# dual_motor_driver_v6.net
KiCad netlist of a schematic drawn in EAGLE
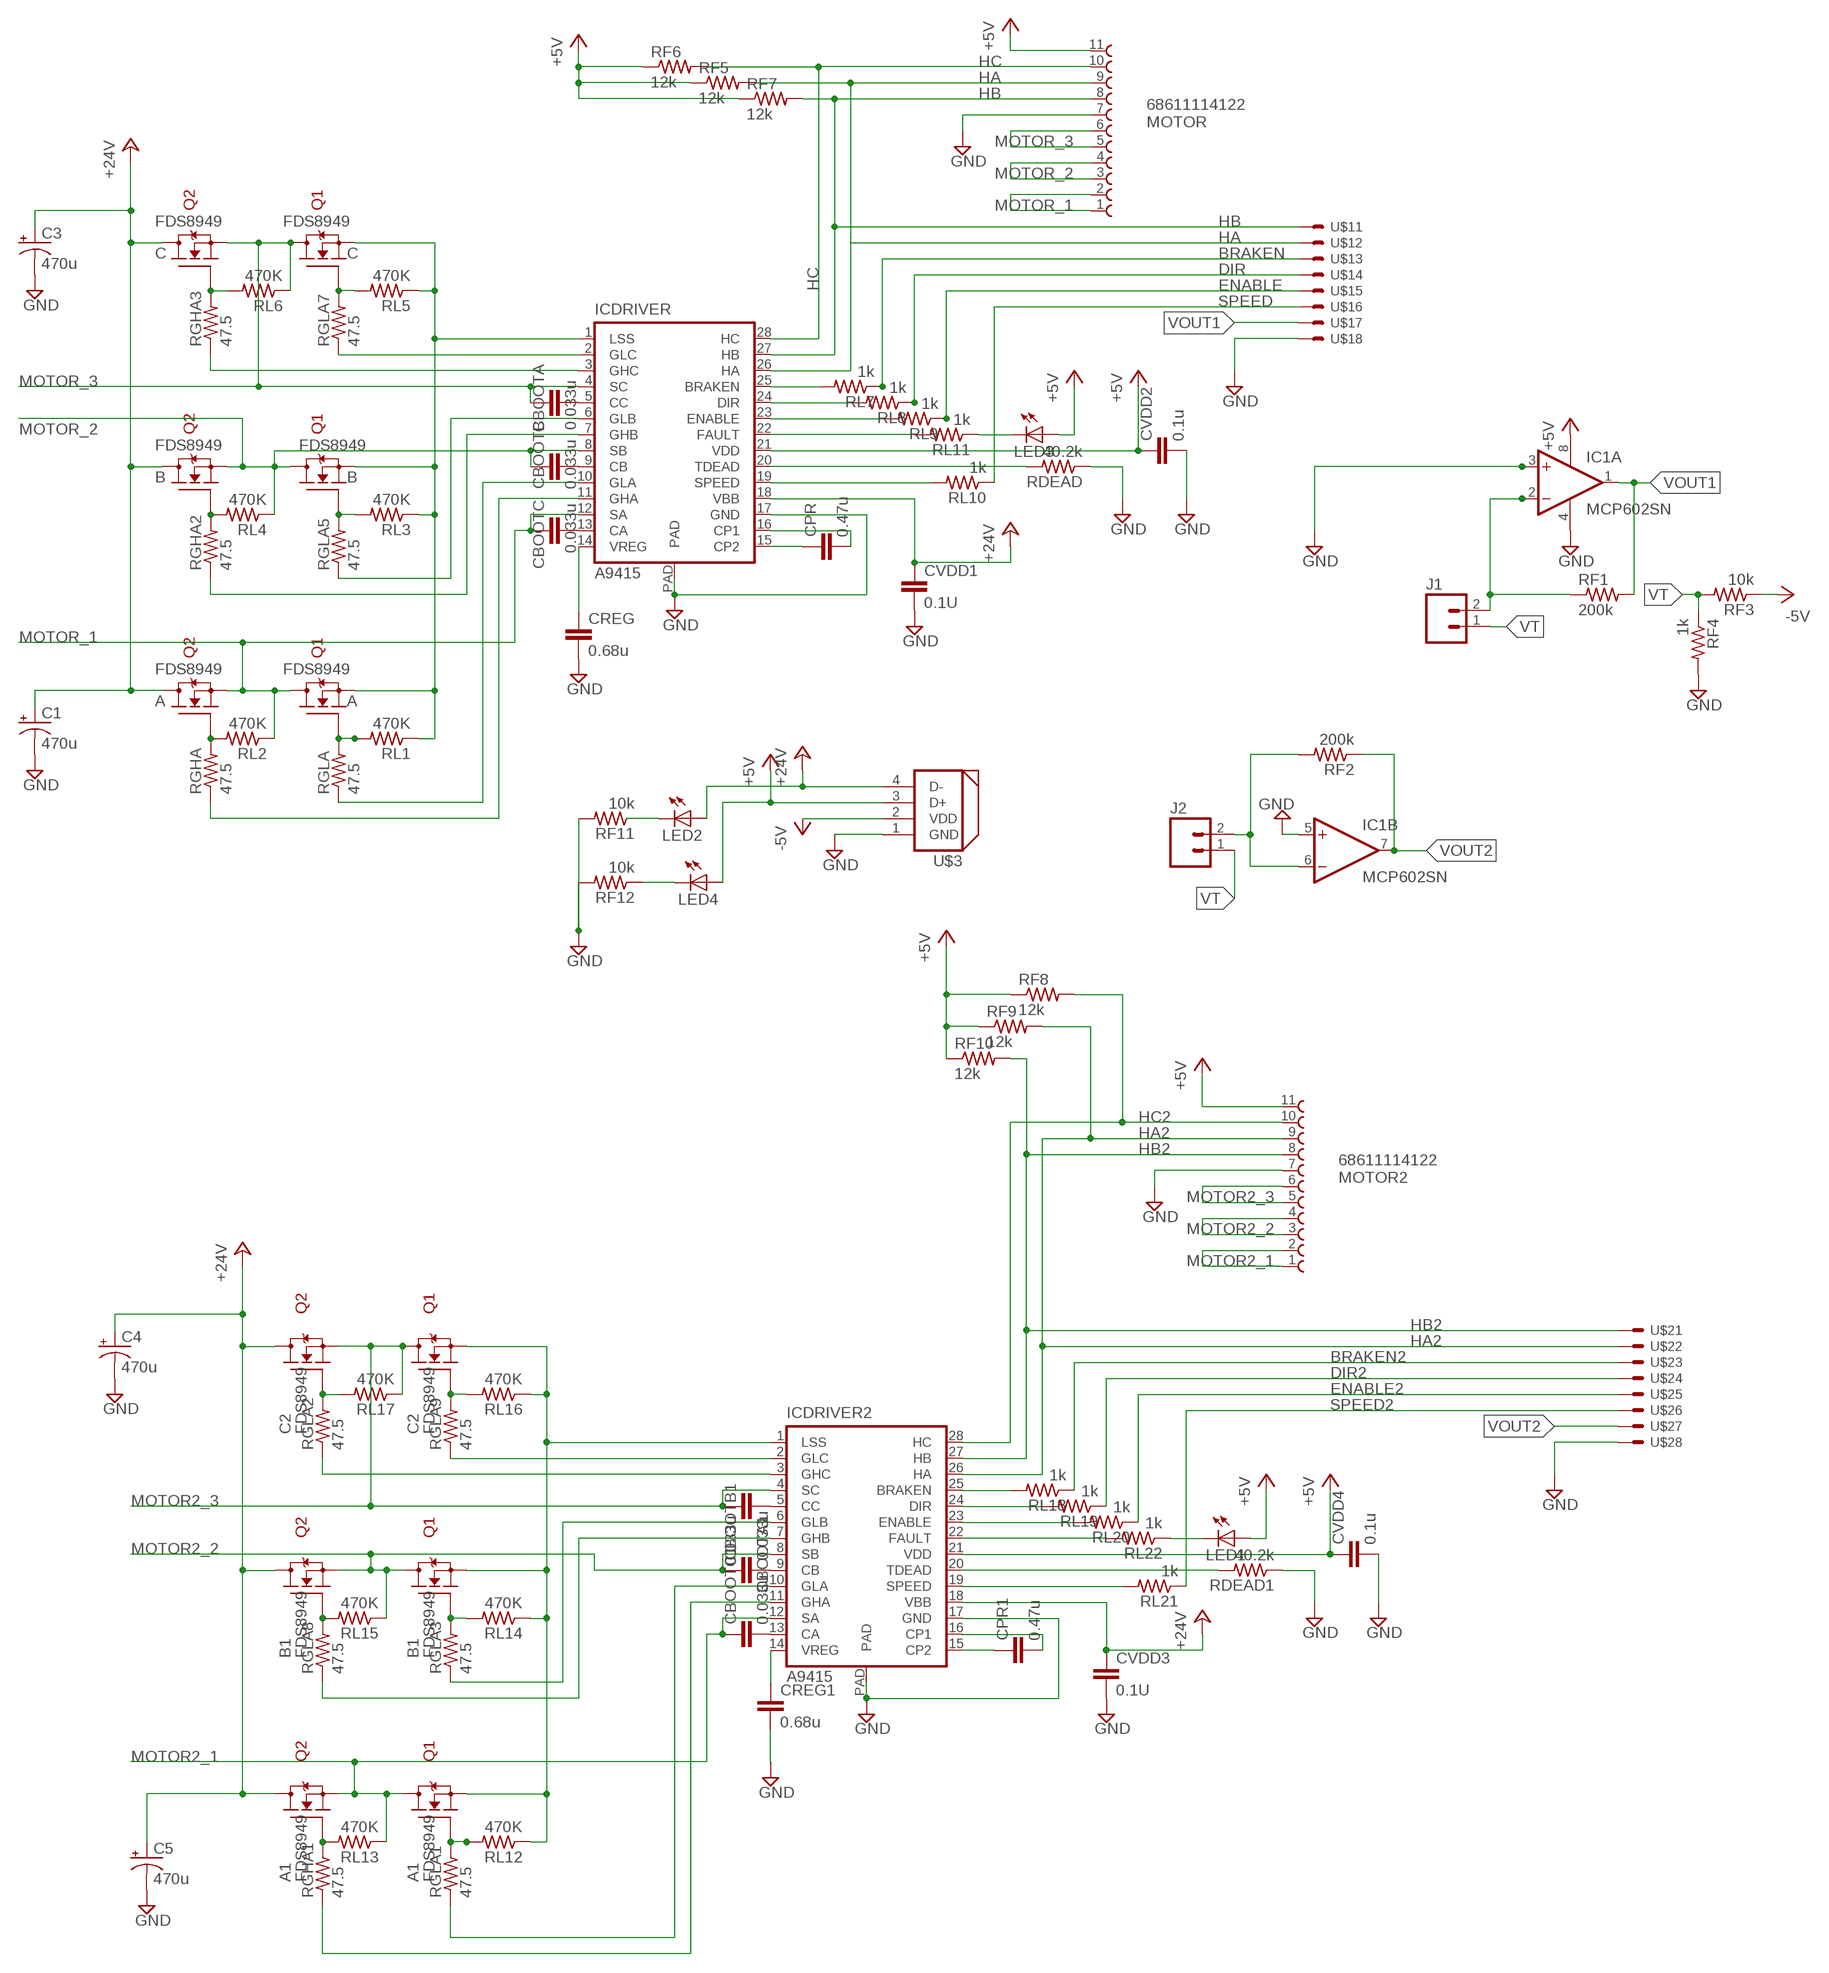
[diagram p0: schematic, sheet 1]

(export (version "E")
  (design (tool "Eeschema 10.0.6"))
  (components
    (comp (ref "A")
      (value "FDS8949")
      (footprint "eagle-import:SOIC8")
      (libsource (lib "eagle-import") (part "FDS8949"))
    )
    (comp (ref "A1")
      (value "FDS8949")
      (footprint "eagle-import:SOIC8")
      (libsource (lib "eagle-import") (part "FDS8949"))
    )
    (comp (ref "B")
      (value "FDS8949")
      (footprint "eagle-import:SOIC8")
      (libsource (lib "eagle-import") (part "FDS8949"))
    )
    (comp (ref "B1")
      (value "FDS8949")
      (footprint "eagle-import:SOIC8")
      (libsource (lib "eagle-import") (part "FDS8949"))
    )
    (comp (ref "C")
      (value "FDS8949")
      (footprint "eagle-import:SOIC8")
      (libsource (lib "eagle-import") (part "FDS8949"))
    )
    (comp (ref "C1")
      (value "470u")
      (footprint "eagle-import:140CLH-1010")
      (libsource (lib "eagle-import") (part "CPOL-US140CLH-1010"))
    )
    (comp (ref "C2")
      (value "FDS8949")
      (footprint "eagle-import:SOIC8")
      (libsource (lib "eagle-import") (part "FDS8949"))
    )
    (comp (ref "C3")
      (value "470u")
      (footprint "eagle-import:140CLH-1010")
      (libsource (lib "eagle-import") (part "CPOL-US140CLH-1010"))
    )
    (comp (ref "C4")
      (value "470u")
      (footprint "eagle-import:140CLH-1010")
      (libsource (lib "eagle-import") (part "CPOL-US140CLH-1010"))
    )
    (comp (ref "C5")
      (value "470u")
      (footprint "eagle-import:140CLH-1010")
      (libsource (lib "eagle-import") (part "CPOL-US140CLH-1010"))
    )
    (comp (ref "CBOOTA")
      (value "0.033u")
      (footprint "eagle-import:C0805")
      (libsource (lib "eagle-import") (part "C-EUC0805"))
    )
    (comp (ref "CBOOTA1")
      (value "0.033u")
      (footprint "eagle-import:C0805")
      (libsource (lib "eagle-import") (part "C-EUC0805"))
    )
    (comp (ref "CBOOTB")
      (value "0.033u")
      (footprint "eagle-import:C0805")
      (libsource (lib "eagle-import") (part "C-EUC0805"))
    )
    (comp (ref "CBOOTB1")
      (value "0.033u")
      (footprint "eagle-import:C0805")
      (libsource (lib "eagle-import") (part "C-EUC0805"))
    )
    (comp (ref "CBOOTC")
      (value "0.033u")
      (footprint "eagle-import:C0805")
      (libsource (lib "eagle-import") (part "C-EUC0805"))
    )
    (comp (ref "CBOOTC1")
      (value "0.033u")
      (footprint "eagle-import:C0805")
      (libsource (lib "eagle-import") (part "C-EUC0805"))
    )
    (comp (ref "CPR")
      (value "0.47u")
      (footprint "eagle-import:C0805")
      (libsource (lib "eagle-import") (part "C-EUC0805"))
    )
    (comp (ref "CPR1")
      (value "0.47u")
      (footprint "eagle-import:C0805")
      (libsource (lib "eagle-import") (part "C-EUC0805"))
    )
    (comp (ref "CREG")
      (value "0.68u")
      (footprint "eagle-import:C0805")
      (libsource (lib "eagle-import") (part "C-EUC0805"))
    )
    (comp (ref "CREG1")
      (value "0.68u")
      (footprint "eagle-import:C0805")
      (libsource (lib "eagle-import") (part "C-EUC0805"))
    )
    (comp (ref "CVDD1")
      (value "0.1U")
      (footprint "eagle-import:C0805")
      (libsource (lib "eagle-import") (part "C-EUC0805"))
    )
    (comp (ref "CVDD2")
      (value "0.1u")
      (footprint "eagle-import:C0805")
      (libsource (lib "eagle-import") (part "C-EUC0805"))
    )
    (comp (ref "CVDD3")
      (value "0.1U")
      (footprint "eagle-import:C0805")
      (libsource (lib "eagle-import") (part "C-EUC0805"))
    )
    (comp (ref "CVDD4")
      (value "0.1u")
      (footprint "eagle-import:C0805")
      (libsource (lib "eagle-import") (part "C-EUC0805"))
    )
    (comp (ref "IC1")
      (value "MCP602SN")
      (footprint "eagle-import:SO08")
      (libsource (lib "eagle-import") (part "MCP602SN"))
    )
    (comp (ref "ICDRIVER")
      (value "A9415")
      (footprint "eagle-import:TSSOP28")
      (libsource (lib "eagle-import") (part "A9415"))
    )
    (comp (ref "ICDRIVER2")
      (value "A9415")
      (footprint "eagle-import:TSSOP28")
      (libsource (lib "eagle-import") (part "A9415"))
    )
    (comp (ref "J1")
      (value "M02PTH")
      (footprint "eagle-import:1X02")
      (libsource (lib "eagle-import") (part "M02PTH"))
    )
    (comp (ref "J2")
      (value "M02PTH")
      (footprint "eagle-import:1X02")
      (libsource (lib "eagle-import") (part "M02PTH"))
    )
    (comp (ref "LED1")
      (value "LEDCHIPLED_0805")
      (footprint "eagle-import:CHIPLED_0805")
      (libsource (lib "eagle-import") (part "LEDCHIPLED_0805"))
    )
    (comp (ref "LED2")
      (value "LEDCHIPLED_0805")
      (footprint "eagle-import:CHIPLED_0805")
      (libsource (lib "eagle-import") (part "LEDCHIPLED_0805"))
    )
    (comp (ref "LED3")
      (value "LEDCHIPLED_0805")
      (footprint "eagle-import:CHIPLED_0805")
      (libsource (lib "eagle-import") (part "LEDCHIPLED_0805"))
    )
    (comp (ref "LED4")
      (value "LEDCHIPLED_0805")
      (footprint "eagle-import:CHIPLED_0805")
      (libsource (lib "eagle-import") (part "LEDCHIPLED_0805"))
    )
    (comp (ref "MOTOR")
      (value "68611114122")
      (footprint "eagle-import:68611114122")
      (libsource (lib "eagle-import") (part "68611114122"))
    )
    (comp (ref "MOTOR2")
      (value "68611114122")
      (footprint "eagle-import:68611114122")
      (libsource (lib "eagle-import") (part "68611114122"))
    )
    (comp (ref "RDEAD")
      (value "40.2k")
      (footprint "eagle-import:R0805")
      (libsource (lib "eagle-import") (part "R-US_R0805"))
    )
    (comp (ref "RDEAD1")
      (value "40.2k")
      (footprint "eagle-import:R0805")
      (libsource (lib "eagle-import") (part "R-US_R0805"))
    )
    (comp (ref "RF1")
      (value "200k")
      (footprint "eagle-import:R0805")
      (libsource (lib "eagle-import") (part "R-US_R0805"))
    )
    (comp (ref "RF2")
      (value "200k")
      (footprint "eagle-import:R0805")
      (libsource (lib "eagle-import") (part "R-US_R0805"))
    )
    (comp (ref "RF3")
      (value "10k")
      (footprint "eagle-import:R0805")
      (libsource (lib "eagle-import") (part "R-US_R0805"))
    )
    (comp (ref "RF4")
      (value "1k")
      (footprint "eagle-import:R0805")
      (libsource (lib "eagle-import") (part "R-US_R0805"))
    )
    (comp (ref "RF5")
      (value "12k")
      (footprint "eagle-import:R0805")
      (libsource (lib "eagle-import") (part "R-US_R0805"))
    )
    (comp (ref "RF6")
      (value "12k")
      (footprint "eagle-import:R0805")
      (libsource (lib "eagle-import") (part "R-US_R0805"))
    )
    (comp (ref "RF7")
      (value "12k")
      (footprint "eagle-import:R0805")
      (libsource (lib "eagle-import") (part "R-US_R0805"))
    )
    (comp (ref "RF8")
      (value "12k")
      (footprint "eagle-import:R0805")
      (libsource (lib "eagle-import") (part "R-US_R0805"))
    )
    (comp (ref "RF9")
      (value "12k")
      (footprint "eagle-import:R0805")
      (libsource (lib "eagle-import") (part "R-US_R0805"))
    )
    (comp (ref "RF10")
      (value "12k")
      (footprint "eagle-import:R0805")
      (libsource (lib "eagle-import") (part "R-US_R0805"))
    )
    (comp (ref "RF11")
      (value "10k")
      (footprint "eagle-import:R0805")
      (libsource (lib "eagle-import") (part "R-US_R0805"))
    )
    (comp (ref "RF12")
      (value "10k")
      (footprint "eagle-import:R0805")
      (libsource (lib "eagle-import") (part "R-US_R0805"))
    )
    (comp (ref "RGHA")
      (value "47.5")
      (footprint "eagle-import:R0805")
      (libsource (lib "eagle-import") (part "R-US_R0805"))
    )
    (comp (ref "RGHA1")
      (value "47.5")
      (footprint "eagle-import:R0805")
      (libsource (lib "eagle-import") (part "R-US_R0805"))
    )
    (comp (ref "RGHA2")
      (value "47.5")
      (footprint "eagle-import:R0805")
      (libsource (lib "eagle-import") (part "R-US_R0805"))
    )
    (comp (ref "RGHA3")
      (value "47.5")
      (footprint "eagle-import:R0805")
      (libsource (lib "eagle-import") (part "R-US_R0805"))
    )
    (comp (ref "RGLA")
      (value "47.5")
      (footprint "eagle-import:R0805")
      (libsource (lib "eagle-import") (part "R-US_R0805"))
    )
    (comp (ref "RGLA1")
      (value "47.5")
      (footprint "eagle-import:R0805")
      (libsource (lib "eagle-import") (part "R-US_R0805"))
    )
    (comp (ref "RGLA2")
      (value "47.5")
      (footprint "eagle-import:R0805")
      (libsource (lib "eagle-import") (part "R-US_R0805"))
    )
    (comp (ref "RGLA3")
      (value "47.5")
      (footprint "eagle-import:R0805")
      (libsource (lib "eagle-import") (part "R-US_R0805"))
    )
    (comp (ref "RGLA5")
      (value "47.5")
      (footprint "eagle-import:R0805")
      (libsource (lib "eagle-import") (part "R-US_R0805"))
    )
    (comp (ref "RGLA7")
      (value "47.5")
      (footprint "eagle-import:R0805")
      (libsource (lib "eagle-import") (part "R-US_R0805"))
    )
    (comp (ref "RGLA8")
      (value "47.5")
      (footprint "eagle-import:R0805")
      (libsource (lib "eagle-import") (part "R-US_R0805"))
    )
    (comp (ref "RGLA9")
      (value "47.5")
      (footprint "eagle-import:R0805")
      (libsource (lib "eagle-import") (part "R-US_R0805"))
    )
    (comp (ref "RL1")
      (value "470K")
      (footprint "eagle-import:R0805")
      (libsource (lib "eagle-import") (part "R-US_R0805"))
    )
    (comp (ref "RL2")
      (value "470K")
      (footprint "eagle-import:R0805")
      (libsource (lib "eagle-import") (part "R-US_R0805"))
    )
    (comp (ref "RL3")
      (value "470K")
      (footprint "eagle-import:R0805")
      (libsource (lib "eagle-import") (part "R-US_R0805"))
    )
    (comp (ref "RL4")
      (value "470K")
      (footprint "eagle-import:R0805")
      (libsource (lib "eagle-import") (part "R-US_R0805"))
    )
    (comp (ref "RL5")
      (value "470K")
      (footprint "eagle-import:R0805")
      (libsource (lib "eagle-import") (part "R-US_R0805"))
    )
    (comp (ref "RL6")
      (value "470K")
      (footprint "eagle-import:R0805")
      (libsource (lib "eagle-import") (part "R-US_R0805"))
    )
    (comp (ref "RL7")
      (value "1k")
      (footprint "eagle-import:R0805")
      (libsource (lib "eagle-import") (part "R-US_R0805"))
    )
    (comp (ref "RL8")
      (value "1k")
      (footprint "eagle-import:R0805")
      (libsource (lib "eagle-import") (part "R-US_R0805"))
    )
    (comp (ref "RL9")
      (value "1k")
      (footprint "eagle-import:R0805")
      (libsource (lib "eagle-import") (part "R-US_R0805"))
    )
    (comp (ref "RL10")
      (value "1k")
      (footprint "eagle-import:R0805")
      (libsource (lib "eagle-import") (part "R-US_R0805"))
    )
    (comp (ref "RL11")
      (value "1k")
      (footprint "eagle-import:R0805")
      (libsource (lib "eagle-import") (part "R-US_R0805"))
    )
    (comp (ref "RL12")
      (value "470K")
      (footprint "eagle-import:R0805")
      (libsource (lib "eagle-import") (part "R-US_R0805"))
    )
    (comp (ref "RL13")
      (value "470K")
      (footprint "eagle-import:R0805")
      (libsource (lib "eagle-import") (part "R-US_R0805"))
    )
    (comp (ref "RL14")
      (value "470K")
      (footprint "eagle-import:R0805")
      (libsource (lib "eagle-import") (part "R-US_R0805"))
    )
    (comp (ref "RL15")
      (value "470K")
      (footprint "eagle-import:R0805")
      (libsource (lib "eagle-import") (part "R-US_R0805"))
    )
    (comp (ref "RL16")
      (value "470K")
      (footprint "eagle-import:R0805")
      (libsource (lib "eagle-import") (part "R-US_R0805"))
    )
    (comp (ref "RL17")
      (value "470K")
      (footprint "eagle-import:R0805")
      (libsource (lib "eagle-import") (part "R-US_R0805"))
    )
    (comp (ref "RL18")
      (value "1k")
      (footprint "eagle-import:R0805")
      (libsource (lib "eagle-import") (part "R-US_R0805"))
    )
    (comp (ref "RL19")
      (value "1k")
      (footprint "eagle-import:R0805")
      (libsource (lib "eagle-import") (part "R-US_R0805"))
    )
    (comp (ref "RL20")
      (value "1k")
      (footprint "eagle-import:R0805")
      (libsource (lib "eagle-import") (part "R-US_R0805"))
    )
    (comp (ref "RL21")
      (value "1k")
      (footprint "eagle-import:R0805")
      (libsource (lib "eagle-import") (part "R-US_R0805"))
    )
    (comp (ref "RL22")
      (value "1k")
      (footprint "eagle-import:R0805")
      (libsource (lib "eagle-import") (part "R-US_R0805"))
    )
    (comp (ref "U$1")
      (value "JST8")
      (footprint "eagle-import:JST")
      (libsource (lib "eagle-import") (part "JST8"))
    )
    (comp (ref "U$2")
      (value "JST8")
      (footprint "eagle-import:JST")
      (libsource (lib "eagle-import") (part "JST8"))
    )
    (comp (ref "U$3")
      (value "DYNAMIXEL_RS485")
      (footprint "eagle-import:DYNAMIXEL_SPOX_04")
      (libsource (lib "eagle-import") (part "DYNAMIXEL_RS485"))
    )
  )
  (nets
    (net (code "1") (name "+5V") (class "Default")
      (node (ref "CVDD2") (pin "1") (pinfunction "1_1") (pintype "passive"))
      (node (ref "CVDD4") (pin "1") (pinfunction "1_1") (pintype "passive"))
      (node (ref "IC1") (pin "8") (pinfunction "V+_8") (pintype "power_in"))
      (node (ref "ICDRIVER") (pin "21") (pinfunction "VDD_21") (pintype "power_in"))
      (node (ref "ICDRIVER2") (pin "21") (pinfunction "VDD_21") (pintype "power_in"))
      (node (ref "LED1") (pin "A") (pinfunction "A_A") (pintype "passive"))
      (node (ref "LED3") (pin "A") (pinfunction "A_A") (pintype "passive"))
      (node (ref "LED4") (pin "A") (pinfunction "A_A") (pintype "passive"))
      (node (ref "MOTOR") (pin "11") (pinfunction "11_11") (pintype "passive"))
      (node (ref "MOTOR2") (pin "11") (pinfunction "11_11") (pintype "passive"))
      (node (ref "RF10") (pin "1") (pinfunction "1_1") (pintype "passive"))
      (node (ref "RF5") (pin "1") (pinfunction "1_1") (pintype "passive"))
      (node (ref "RF6") (pin "1") (pinfunction "1_1") (pintype "passive"))
      (node (ref "RF7") (pin "1") (pinfunction "1_1") (pintype "passive"))
      (node (ref "RF8") (pin "1") (pinfunction "1_1") (pintype "passive"))
      (node (ref "RF9") (pin "1") (pinfunction "1_1") (pintype "passive"))
      (node (ref "U$3") (pin "3") (pinfunction "D+_3") (pintype "bidirectional"))
    )
    (net (code "2") (name "+24V") (class "Default")
      (node (ref "A") (pin "5") (pinfunction "D2_5") (pintype "passive"))
      (node (ref "A") (pin "6") (pinfunction "D2_6") (pintype "passive"))
      (node (ref "A1") (pin "5") (pinfunction "D2_5") (pintype "passive"))
      (node (ref "A1") (pin "6") (pinfunction "D2_6") (pintype "passive"))
      (node (ref "B") (pin "5") (pinfunction "D2_5") (pintype "passive"))
      (node (ref "B") (pin "6") (pinfunction "D2_6") (pintype "passive"))
      (node (ref "B1") (pin "5") (pinfunction "D2_5") (pintype "passive"))
      (node (ref "B1") (pin "6") (pinfunction "D2_6") (pintype "passive"))
      (node (ref "C") (pin "5") (pinfunction "D2_5") (pintype "passive"))
      (node (ref "C") (pin "6") (pinfunction "D2_6") (pintype "passive"))
      (node (ref "C1") (pin "+") (pinfunction "+_+") (pintype "passive"))
      (node (ref "C2") (pin "5") (pinfunction "D2_5") (pintype "passive"))
      (node (ref "C2") (pin "6") (pinfunction "D2_6") (pintype "passive"))
      (node (ref "C3") (pin "+") (pinfunction "+_+") (pintype "passive"))
      (node (ref "C4") (pin "+") (pinfunction "+_+") (pintype "passive"))
      (node (ref "C5") (pin "+") (pinfunction "+_+") (pintype "passive"))
      (node (ref "CVDD1") (pin "1") (pinfunction "1_1") (pintype "passive"))
      (node (ref "CVDD3") (pin "1") (pinfunction "1_1") (pintype "passive"))
      (node (ref "ICDRIVER") (pin "18") (pinfunction "VBB_18") (pintype "power_in"))
      (node (ref "ICDRIVER2") (pin "18") (pinfunction "VBB_18") (pintype "power_in"))
      (node (ref "LED2") (pin "A") (pinfunction "A_A") (pintype "passive"))
      (node (ref "U$3") (pin "4") (pinfunction "D-_4") (pintype "bidirectional"))
    )
    (net (code "3") (name "-5V") (class "Default")
      (node (ref "RF3") (pin "1") (pinfunction "1_1") (pintype "passive"))
      (node (ref "U$3") (pin "2") (pinfunction "VDD_2") (pintype "power_in"))
    )
    (net (code "4") (name "/BRAKEN") (class "Default")
      (node (ref "RL7") (pin "1") (pinfunction "1_1") (pintype "passive"))
      (node (ref "U$1") (pin "3") (pinfunction "S_3") (pintype "passive"))
    )
    (net (code "5") (name "/BRAKEN2") (class "Default")
      (node (ref "RL18") (pin "1") (pinfunction "1_1") (pintype "passive"))
      (node (ref "U$2") (pin "3") (pinfunction "S_3") (pintype "passive"))
    )
    (net (code "6") (name "/DIR") (class "Default")
      (node (ref "RL8") (pin "1") (pinfunction "1_1") (pintype "passive"))
      (node (ref "U$1") (pin "4") (pinfunction "S_4") (pintype "passive"))
    )
    (net (code "7") (name "/DIR2") (class "Default")
      (node (ref "RL19") (pin "1") (pinfunction "1_1") (pintype "passive"))
      (node (ref "U$2") (pin "4") (pinfunction "S_4") (pintype "passive"))
    )
    (net (code "8") (name "/ENABLE") (class "Default")
      (node (ref "RL9") (pin "1") (pinfunction "1_1") (pintype "passive"))
      (node (ref "U$1") (pin "5") (pinfunction "S_5") (pintype "passive"))
    )
    (net (code "9") (name "/ENABLE2") (class "Default")
      (node (ref "RL20") (pin "1") (pinfunction "1_1") (pintype "passive"))
      (node (ref "U$2") (pin "5") (pinfunction "S_5") (pintype "passive"))
    )
    (net (code "10") (name "/HA") (class "Default")
      (node (ref "ICDRIVER") (pin "26") (pinfunction "HA_26") (pintype "input"))
      (node (ref "MOTOR") (pin "9") (pinfunction "9_9") (pintype "passive"))
      (node (ref "RF5") (pin "2") (pinfunction "2_2") (pintype "passive"))
      (node (ref "U$1") (pin "2") (pinfunction "S_2") (pintype "passive"))
    )
    (net (code "11") (name "/HA2") (class "Default")
      (node (ref "ICDRIVER2") (pin "26") (pinfunction "HA_26") (pintype "input"))
      (node (ref "MOTOR2") (pin "9") (pinfunction "9_9") (pintype "passive"))
      (node (ref "RF9") (pin "2") (pinfunction "2_2") (pintype "passive"))
      (node (ref "U$2") (pin "2") (pinfunction "S_2") (pintype "passive"))
    )
    (net (code "12") (name "/HB") (class "Default")
      (node (ref "ICDRIVER") (pin "27") (pinfunction "HB_27") (pintype "input"))
      (node (ref "MOTOR") (pin "8") (pinfunction "8_8") (pintype "passive"))
      (node (ref "RF7") (pin "2") (pinfunction "2_2") (pintype "passive"))
      (node (ref "U$1") (pin "1") (pinfunction "S_1") (pintype "passive"))
    )
    (net (code "13") (name "/HB2") (class "Default")
      (node (ref "ICDRIVER2") (pin "27") (pinfunction "HB_27") (pintype "input"))
      (node (ref "MOTOR2") (pin "8") (pinfunction "8_8") (pintype "passive"))
      (node (ref "RF10") (pin "2") (pinfunction "2_2") (pintype "passive"))
      (node (ref "U$2") (pin "1") (pinfunction "S_1") (pintype "passive"))
    )
    (net (code "14") (name "/HC") (class "Default")
      (node (ref "ICDRIVER") (pin "28") (pinfunction "HC_28") (pintype "input"))
      (node (ref "MOTOR") (pin "10") (pinfunction "10_10") (pintype "passive"))
      (node (ref "RF6") (pin "2") (pinfunction "2_2") (pintype "passive"))
    )
    (net (code "15") (name "/HC2") (class "Default")
      (node (ref "ICDRIVER2") (pin "28") (pinfunction "HC_28") (pintype "input"))
      (node (ref "MOTOR2") (pin "10") (pinfunction "10_10") (pintype "passive"))
      (node (ref "RF8") (pin "2") (pinfunction "2_2") (pintype "passive"))
    )
    (net (code "16") (name "/MOTOR2_1") (class "Default")
      (node (ref "A1") (pin "3") (pinfunction "S2_3") (pintype "passive"))
      (node (ref "A1") (pin "7") (pinfunction "D1_7") (pintype "passive"))
      (node (ref "A1") (pin "8") (pinfunction "D1_8") (pintype "passive"))
      (node (ref "CBOOTC1") (pin "1") (pinfunction "1_1") (pintype "passive"))
      (node (ref "ICDRIVER2") (pin "12") (pinfunction "SA_12") (pintype "output"))
      (node (ref "MOTOR2") (pin "1") (pinfunction "1_1") (pintype "passive"))
      (node (ref "MOTOR2") (pin "2") (pinfunction "2_2") (pintype "passive"))
      (node (ref "RL13") (pin "1") (pinfunction "1_1") (pintype "passive"))
    )
    (net (code "17") (name "/MOTOR2_2") (class "Default")
      (node (ref "B1") (pin "3") (pinfunction "S2_3") (pintype "passive"))
      (node (ref "B1") (pin "7") (pinfunction "D1_7") (pintype "passive"))
      (node (ref "B1") (pin "8") (pinfunction "D1_8") (pintype "passive"))
      (node (ref "CBOOTB1") (pin "1") (pinfunction "1_1") (pintype "passive"))
      (node (ref "ICDRIVER2") (pin "8") (pinfunction "SB_8") (pintype "output"))
      (node (ref "MOTOR2") (pin "3") (pinfunction "3_3") (pintype "passive"))
      (node (ref "MOTOR2") (pin "4") (pinfunction "4_4") (pintype "passive"))
      (node (ref "RL15") (pin "1") (pinfunction "1_1") (pintype "passive"))
    )
    (net (code "18") (name "/MOTOR2_3") (class "Default")
      (node (ref "C2") (pin "3") (pinfunction "S2_3") (pintype "passive"))
      (node (ref "C2") (pin "7") (pinfunction "D1_7") (pintype "passive"))
      (node (ref "C2") (pin "8") (pinfunction "D1_8") (pintype "passive"))
      (node (ref "CBOOTA1") (pin "2") (pinfunction "2_2") (pintype "passive"))
      (node (ref "ICDRIVER2") (pin "4") (pinfunction "SC_4") (pintype "output"))
      (node (ref "MOTOR2") (pin "5") (pinfunction "5_5") (pintype "passive"))
      (node (ref "MOTOR2") (pin "6") (pinfunction "6_6") (pintype "passive"))
      (node (ref "RL17") (pin "1") (pinfunction "1_1") (pintype "passive"))
    )
    (net (code "19") (name "/MOTOR_1") (class "Default")
      (node (ref "A") (pin "3") (pinfunction "S2_3") (pintype "passive"))
      (node (ref "A") (pin "7") (pinfunction "D1_7") (pintype "passive"))
      (node (ref "A") (pin "8") (pinfunction "D1_8") (pintype "passive"))
      (node (ref "CBOOTC") (pin "1") (pinfunction "1_1") (pintype "passive"))
      (node (ref "ICDRIVER") (pin "12") (pinfunction "SA_12") (pintype "output"))
      (node (ref "MOTOR") (pin "1") (pinfunction "1_1") (pintype "passive"))
      (node (ref "MOTOR") (pin "2") (pinfunction "2_2") (pintype "passive"))
      (node (ref "RL2") (pin "1") (pinfunction "1_1") (pintype "passive"))
    )
    (net (code "20") (name "/MOTOR_2") (class "Default")
      (node (ref "B") (pin "3") (pinfunction "S2_3") (pintype "passive"))
      (node (ref "B") (pin "7") (pinfunction "D1_7") (pintype "passive"))
      (node (ref "B") (pin "8") (pinfunction "D1_8") (pintype "passive"))
      (node (ref "CBOOTB") (pin "1") (pinfunction "1_1") (pintype "passive"))
      (node (ref "ICDRIVER") (pin "8") (pinfunction "SB_8") (pintype "output"))
      (node (ref "MOTOR") (pin "3") (pinfunction "3_3") (pintype "passive"))
      (node (ref "MOTOR") (pin "4") (pinfunction "4_4") (pintype "passive"))
      (node (ref "RL4") (pin "1") (pinfunction "1_1") (pintype "passive"))
    )
    (net (code "21") (name "/MOTOR_3") (class "Default")
      (node (ref "C") (pin "3") (pinfunction "S2_3") (pintype "passive"))
      (node (ref "C") (pin "7") (pinfunction "D1_7") (pintype "passive"))
      (node (ref "C") (pin "8") (pinfunction "D1_8") (pintype "passive"))
      (node (ref "CBOOTA") (pin "2") (pinfunction "2_2") (pintype "passive"))
      (node (ref "ICDRIVER") (pin "4") (pinfunction "SC_4") (pintype "output"))
      (node (ref "MOTOR") (pin "5") (pinfunction "5_5") (pintype "passive"))
      (node (ref "MOTOR") (pin "6") (pinfunction "6_6") (pintype "passive"))
      (node (ref "RL6") (pin "1") (pinfunction "1_1") (pintype "passive"))
    )
    (net (code "22") (name "/SPEED") (class "Default")
      (node (ref "RL10") (pin "1") (pinfunction "1_1") (pintype "passive"))
      (node (ref "U$1") (pin "6") (pinfunction "S_6") (pintype "passive"))
    )
    (net (code "23") (name "/SPEED2") (class "Default")
      (node (ref "RL21") (pin "1") (pinfunction "1_1") (pintype "passive"))
      (node (ref "U$2") (pin "6") (pinfunction "S_6") (pintype "passive"))
    )
    (net (code "24") (name "GND") (class "Default")
      (node (ref "A") (pin "1") (pinfunction "S1_1") (pintype "passive"))
      (node (ref "A1") (pin "1") (pinfunction "S1_1") (pintype "passive"))
      (node (ref "B") (pin "1") (pinfunction "S1_1") (pintype "passive"))
      (node (ref "B1") (pin "1") (pinfunction "S1_1") (pintype "passive"))
      (node (ref "C") (pin "1") (pinfunction "S1_1") (pintype "passive"))
      (node (ref "C1") (pin "-") (pinfunction "-_-") (pintype "passive"))
      (node (ref "C2") (pin "1") (pinfunction "S1_1") (pintype "passive"))
      (node (ref "C3") (pin "-") (pinfunction "-_-") (pintype "passive"))
      (node (ref "C4") (pin "-") (pinfunction "-_-") (pintype "passive"))
      (node (ref "C5") (pin "-") (pinfunction "-_-") (pintype "passive"))
      (node (ref "CREG") (pin "2") (pinfunction "2_2") (pintype "passive"))
      (node (ref "CREG1") (pin "2") (pinfunction "2_2") (pintype "passive"))
      (node (ref "CVDD1") (pin "2") (pinfunction "2_2") (pintype "passive"))
      (node (ref "CVDD2") (pin "2") (pinfunction "2_2") (pintype "passive"))
      (node (ref "CVDD3") (pin "2") (pinfunction "2_2") (pintype "passive"))
      (node (ref "CVDD4") (pin "2") (pinfunction "2_2") (pintype "passive"))
      (node (ref "IC1") (pin "3") (pinfunction "+IN_3") (pintype "input"))
      (node (ref "IC1") (pin "4") (pinfunction "V-_4") (pintype "power_in"))
      (node (ref "IC1") (pin "5") (pinfunction "+IN_5") (pintype "input"))
      (node (ref "ICDRIVER") (pin "1") (pinfunction "LSS_1") (pintype "input"))
      (node (ref "ICDRIVER") (pin "17") (pinfunction "GND_17") (pintype "power_in"))
      (node (ref "ICDRIVER") (pin "PAD") (pinfunction "PAD_PAD") (pintype "power_in"))
      (node (ref "ICDRIVER2") (pin "1") (pinfunction "LSS_1") (pintype "input"))
      (node (ref "ICDRIVER2") (pin "17") (pinfunction "GND_17") (pintype "power_in"))
      (node (ref "ICDRIVER2") (pin "PAD") (pinfunction "PAD_PAD") (pintype "power_in"))
      (node (ref "MOTOR") (pin "7") (pinfunction "7_7") (pintype "passive"))
      (node (ref "MOTOR2") (pin "7") (pinfunction "7_7") (pintype "passive"))
      (node (ref "RDEAD") (pin "1") (pinfunction "1_1") (pintype "passive"))
      (node (ref "RDEAD1") (pin "1") (pinfunction "1_1") (pintype "passive"))
      (node (ref "RF11") (pin "2") (pinfunction "2_2") (pintype "passive"))
      (node (ref "RF12") (pin "2") (pinfunction "2_2") (pintype "passive"))
      (node (ref "RF4") (pin "2") (pinfunction "2_2") (pintype "passive"))
      (node (ref "RL1") (pin "1") (pinfunction "1_1") (pintype "passive"))
      (node (ref "RL12") (pin "1") (pinfunction "1_1") (pintype "passive"))
      (node (ref "RL14") (pin "1") (pinfunction "1_1") (pintype "passive"))
      (node (ref "RL16") (pin "1") (pinfunction "1_1") (pintype "passive"))
      (node (ref "RL3") (pin "1") (pinfunction "1_1") (pintype "passive"))
      (node (ref "RL5") (pin "1") (pinfunction "1_1") (pintype "passive"))
      (node (ref "U$1") (pin "8") (pinfunction "S_8") (pintype "passive"))
      (node (ref "U$2") (pin "8") (pinfunction "S_8") (pintype "passive"))
      (node (ref "U$3") (pin "1") (pinfunction "GND_1") (pintype "power_in"))
    )
    (net (code "25") (name "Net-(A-G1)") (class "Default")
      (node (ref "A") (pin "2") (pinfunction "G1_2") (pintype "passive"))
      (node (ref "RGLA") (pin "2") (pinfunction "2_2") (pintype "passive"))
      (node (ref "RL1") (pin "2") (pinfunction "2_2") (pintype "passive"))
    )
    (net (code "26") (name "Net-(A-G2)") (class "Default")
      (node (ref "A") (pin "4") (pinfunction "G2_4") (pintype "passive"))
      (node (ref "RGHA") (pin "2") (pinfunction "2_2") (pintype "passive"))
      (node (ref "RL2") (pin "2") (pinfunction "2_2") (pintype "passive"))
    )
    (net (code "27") (name "Net-(A1-G1)") (class "Default")
      (node (ref "A1") (pin "2") (pinfunction "G1_2") (pintype "passive"))
      (node (ref "RGLA1") (pin "2") (pinfunction "2_2") (pintype "passive"))
      (node (ref "RL12") (pin "2") (pinfunction "2_2") (pintype "passive"))
    )
    (net (code "28") (name "Net-(A1-G2)") (class "Default")
      (node (ref "A1") (pin "4") (pinfunction "G2_4") (pintype "passive"))
      (node (ref "RGHA1") (pin "2") (pinfunction "2_2") (pintype "passive"))
      (node (ref "RL13") (pin "2") (pinfunction "2_2") (pintype "passive"))
    )
    (net (code "29") (name "Net-(B-G1)") (class "Default")
      (node (ref "B") (pin "2") (pinfunction "G1_2") (pintype "passive"))
      (node (ref "RGLA5") (pin "2") (pinfunction "2_2") (pintype "passive"))
      (node (ref "RL3") (pin "2") (pinfunction "2_2") (pintype "passive"))
    )
    (net (code "30") (name "Net-(B-G2)") (class "Default")
      (node (ref "B") (pin "4") (pinfunction "G2_4") (pintype "passive"))
      (node (ref "RGHA2") (pin "2") (pinfunction "2_2") (pintype "passive"))
      (node (ref "RL4") (pin "2") (pinfunction "2_2") (pintype "passive"))
    )
    (net (code "31") (name "Net-(B1-G1)") (class "Default")
      (node (ref "B1") (pin "2") (pinfunction "G1_2") (pintype "passive"))
      (node (ref "RGLA3") (pin "2") (pinfunction "2_2") (pintype "passive"))
      (node (ref "RL14") (pin "2") (pinfunction "2_2") (pintype "passive"))
    )
    (net (code "32") (name "Net-(B1-G2)") (class "Default")
      (node (ref "B1") (pin "4") (pinfunction "G2_4") (pintype "passive"))
      (node (ref "RGLA8") (pin "2") (pinfunction "2_2") (pintype "passive"))
      (node (ref "RL15") (pin "2") (pinfunction "2_2") (pintype "passive"))
    )
    (net (code "33") (name "Net-(C-G1)") (class "Default")
      (node (ref "C") (pin "2") (pinfunction "G1_2") (pintype "passive"))
      (node (ref "RGLA7") (pin "2") (pinfunction "2_2") (pintype "passive"))
      (node (ref "RL5") (pin "2") (pinfunction "2_2") (pintype "passive"))
    )
    (net (code "34") (name "Net-(C-G2)") (class "Default")
      (node (ref "C") (pin "4") (pinfunction "G2_4") (pintype "passive"))
      (node (ref "RGHA3") (pin "2") (pinfunction "2_2") (pintype "passive"))
      (node (ref "RL6") (pin "2") (pinfunction "2_2") (pintype "passive"))
    )
    (net (code "35") (name "Net-(C2-G1)") (class "Default")
      (node (ref "C2") (pin "2") (pinfunction "G1_2") (pintype "passive"))
      (node (ref "RGLA9") (pin "2") (pinfunction "2_2") (pintype "passive"))
      (node (ref "RL16") (pin "2") (pinfunction "2_2") (pintype "passive"))
    )
    (net (code "36") (name "Net-(C2-G2)") (class "Default")
      (node (ref "C2") (pin "4") (pinfunction "G2_4") (pintype "passive"))
      (node (ref "RGLA2") (pin "2") (pinfunction "2_2") (pintype "passive"))
      (node (ref "RL17") (pin "2") (pinfunction "2_2") (pintype "passive"))
    )
    (net (code "37") (name "Net-(IC1A--IN)") (class "Default")
      (node (ref "IC1") (pin "2") (pinfunction "-IN_2") (pintype "input"))
      (node (ref "J1") (pin "2") (pinfunction "2_2") (pintype "passive"))
      (node (ref "RF1") (pin "1") (pinfunction "1_1") (pintype "passive"))
    )
    (net (code "38") (name "Net-(IC1B--IN)") (class "Default")
      (node (ref "IC1") (pin "6") (pinfunction "-IN_6") (pintype "input"))
      (node (ref "J2") (pin "2") (pinfunction "2_2") (pintype "passive"))
      (node (ref "RF2") (pin "2") (pinfunction "2_2") (pintype "passive"))
    )
    (net (code "39") (name "Net-(ICDRIVER-BRAKEN)") (class "Default")
      (node (ref "ICDRIVER") (pin "25") (pinfunction "BRAKEN_25") (pintype "bidirectional"))
      (node (ref "RL7") (pin "2") (pinfunction "2_2") (pintype "passive"))
    )
    (net (code "40") (name "Net-(ICDRIVER-CA)") (class "Default")
      (node (ref "CBOOTC") (pin "2") (pinfunction "2_2") (pintype "passive"))
      (node (ref "ICDRIVER") (pin "13") (pinfunction "CA_13") (pintype "output"))
    )
    (net (code "41") (name "Net-(ICDRIVER-CB)") (class "Default")
      (node (ref "CBOOTB") (pin "2") (pinfunction "2_2") (pintype "passive"))
      (node (ref "ICDRIVER") (pin "9") (pinfunction "CB_9") (pintype "output"))
    )
    (net (code "42") (name "Net-(ICDRIVER-CC)") (class "Default")
      (node (ref "CBOOTA") (pin "1") (pinfunction "1_1") (pintype "passive"))
      (node (ref "ICDRIVER") (pin "5") (pinfunction "CC_5") (pintype "output"))
    )
    (net (code "43") (name "Net-(ICDRIVER-CP1)") (class "Default")
      (node (ref "CPR") (pin "2") (pinfunction "2_2") (pintype "passive"))
      (node (ref "ICDRIVER") (pin "16") (pinfunction "CP1_16") (pintype "input"))
    )
    (net (code "44") (name "Net-(ICDRIVER-CP2)") (class "Default")
      (node (ref "CPR") (pin "1") (pinfunction "1_1") (pintype "passive"))
      (node (ref "ICDRIVER") (pin "15") (pinfunction "CP2_15") (pintype "passive"))
    )
    (net (code "45") (name "Net-(ICDRIVER-DIR)") (class "Default")
      (node (ref "ICDRIVER") (pin "24") (pinfunction "DIR_24") (pintype "input"))
      (node (ref "RL8") (pin "2") (pinfunction "2_2") (pintype "passive"))
    )
    (net (code "46") (name "Net-(ICDRIVER-ENABLE)") (class "Default")
      (node (ref "ICDRIVER") (pin "23") (pinfunction "ENABLE_23") (pintype "input"))
      (node (ref "RL9") (pin "2") (pinfunction "2_2") (pintype "passive"))
    )
    (net (code "47") (name "Net-(ICDRIVER-FAULT)") (class "Default")
      (node (ref "ICDRIVER") (pin "22") (pinfunction "FAULT_22") (pintype "output"))
      (node (ref "RL11") (pin "2") (pinfunction "2_2") (pintype "passive"))
    )
    (net (code "48") (name "Net-(ICDRIVER-GHA)") (class "Default")
      (node (ref "ICDRIVER") (pin "11") (pinfunction "GHA_11") (pintype "output"))
      (node (ref "RGHA") (pin "1") (pinfunction "1_1") (pintype "passive"))
    )
    (net (code "49") (name "Net-(ICDRIVER-GHB)") (class "Default")
      (node (ref "ICDRIVER") (pin "7") (pinfunction "GHB_7") (pintype "output"))
      (node (ref "RGHA2") (pin "1") (pinfunction "1_1") (pintype "passive"))
    )
    (net (code "50") (name "Net-(ICDRIVER-GHC)") (class "Default")
      (node (ref "ICDRIVER") (pin "3") (pinfunction "GHC_3") (pintype "output"))
      (node (ref "RGHA3") (pin "1") (pinfunction "1_1") (pintype "passive"))
    )
    (net (code "51") (name "Net-(ICDRIVER-GLA)") (class "Default")
      (node (ref "ICDRIVER") (pin "10") (pinfunction "GLA_10") (pintype "output"))
      (node (ref "RGLA") (pin "1") (pinfunction "1_1") (pintype "passive"))
    )
    (net (code "52") (name "Net-(ICDRIVER-GLB)") (class "Default")
      (node (ref "ICDRIVER") (pin "6") (pinfunction "GLB_6") (pintype "output"))
      (node (ref "RGLA5") (pin "1") (pinfunction "1_1") (pintype "passive"))
    )
    (net (code "53") (name "Net-(ICDRIVER-GLC)") (class "Default")
      (node (ref "ICDRIVER") (pin "2") (pinfunction "GLC_2") (pintype "output"))
      (node (ref "RGLA7") (pin "1") (pinfunction "1_1") (pintype "passive"))
    )
    (net (code "54") (name "Net-(ICDRIVER-SPEED)") (class "Default")
      (node (ref "ICDRIVER") (pin "19") (pinfunction "SPEED_19") (pintype "input"))
      (node (ref "RL10") (pin "2") (pinfunction "2_2") (pintype "passive"))
    )
    (net (code "55") (name "Net-(ICDRIVER-TDEAD)") (class "Default")
      (node (ref "ICDRIVER") (pin "20") (pinfunction "TDEAD_20") (pintype "input"))
      (node (ref "RDEAD") (pin "2") (pinfunction "2_2") (pintype "passive"))
    )
    (net (code "56") (name "Net-(ICDRIVER-VREG)") (class "Default")
      (node (ref "CREG") (pin "1") (pinfunction "1_1") (pintype "passive"))
      (node (ref "ICDRIVER") (pin "14") (pinfunction "VREG_14") (pintype "power_in"))
    )
    (net (code "57") (name "Net-(ICDRIVER2-BRAKEN)") (class "Default")
      (node (ref "ICDRIVER2") (pin "25") (pinfunction "BRAKEN_25") (pintype "bidirectional"))
      (node (ref "RL18") (pin "2") (pinfunction "2_2") (pintype "passive"))
    )
    (net (code "58") (name "Net-(ICDRIVER2-CA)") (class "Default")
      (node (ref "CBOOTC1") (pin "2") (pinfunction "2_2") (pintype "passive"))
      (node (ref "ICDRIVER2") (pin "13") (pinfunction "CA_13") (pintype "output"))
    )
    (net (code "59") (name "Net-(ICDRIVER2-CB)") (class "Default")
      (node (ref "CBOOTB1") (pin "2") (pinfunction "2_2") (pintype "passive"))
      (node (ref "ICDRIVER2") (pin "9") (pinfunction "CB_9") (pintype "output"))
    )
    (net (code "60") (name "Net-(ICDRIVER2-CC)") (class "Default")
      (node (ref "CBOOTA1") (pin "1") (pinfunction "1_1") (pintype "passive"))
      (node (ref "ICDRIVER2") (pin "5") (pinfunction "CC_5") (pintype "output"))
    )
    (net (code "61") (name "Net-(ICDRIVER2-CP1)") (class "Default")
      (node (ref "CPR1") (pin "2") (pinfunction "2_2") (pintype "passive"))
      (node (ref "ICDRIVER2") (pin "16") (pinfunction "CP1_16") (pintype "input"))
    )
    (net (code "62") (name "Net-(ICDRIVER2-CP2)") (class "Default")
      (node (ref "CPR1") (pin "1") (pinfunction "1_1") (pintype "passive"))
      (node (ref "ICDRIVER2") (pin "15") (pinfunction "CP2_15") (pintype "passive"))
    )
    (net (code "63") (name "Net-(ICDRIVER2-DIR)") (class "Default")
      (node (ref "ICDRIVER2") (pin "24") (pinfunction "DIR_24") (pintype "input"))
      (node (ref "RL19") (pin "2") (pinfunction "2_2") (pintype "passive"))
    )
    (net (code "64") (name "Net-(ICDRIVER2-ENABLE)") (class "Default")
      (node (ref "ICDRIVER2") (pin "23") (pinfunction "ENABLE_23") (pintype "input"))
      (node (ref "RL20") (pin "2") (pinfunction "2_2") (pintype "passive"))
    )
    (net (code "65") (name "Net-(ICDRIVER2-FAULT)") (class "Default")
      (node (ref "ICDRIVER2") (pin "22") (pinfunction "FAULT_22") (pintype "output"))
      (node (ref "RL22") (pin "2") (pinfunction "2_2") (pintype "passive"))
    )
    (net (code "66") (name "Net-(ICDRIVER2-GHA)") (class "Default")
      (node (ref "ICDRIVER2") (pin "11") (pinfunction "GHA_11") (pintype "output"))
      (node (ref "RGHA1") (pin "1") (pinfunction "1_1") (pintype "passive"))
    )
    (net (code "67") (name "Net-(ICDRIVER2-GHB)") (class "Default")
      (node (ref "ICDRIVER2") (pin "7") (pinfunction "GHB_7") (pintype "output"))
      (node (ref "RGLA8") (pin "1") (pinfunction "1_1") (pintype "passive"))
    )
    (net (code "68") (name "Net-(ICDRIVER2-GHC)") (class "Default")
      (node (ref "ICDRIVER2") (pin "3") (pinfunction "GHC_3") (pintype "output"))
      (node (ref "RGLA2") (pin "1") (pinfunction "1_1") (pintype "passive"))
    )
    (net (code "69") (name "Net-(ICDRIVER2-GLA)") (class "Default")
      (node (ref "ICDRIVER2") (pin "10") (pinfunction "GLA_10") (pintype "output"))
      (node (ref "RGLA1") (pin "1") (pinfunction "1_1") (pintype "passive"))
    )
    (net (code "70") (name "Net-(ICDRIVER2-GLB)") (class "Default")
      (node (ref "ICDRIVER2") (pin "6") (pinfunction "GLB_6") (pintype "output"))
      (node (ref "RGLA3") (pin "1") (pinfunction "1_1") (pintype "passive"))
    )
    (net (code "71") (name "Net-(ICDRIVER2-GLC)") (class "Default")
      (node (ref "ICDRIVER2") (pin "2") (pinfunction "GLC_2") (pintype "output"))
      (node (ref "RGLA9") (pin "1") (pinfunction "1_1") (pintype "passive"))
    )
    (net (code "72") (name "Net-(ICDRIVER2-SPEED)") (class "Default")
      (node (ref "ICDRIVER2") (pin "19") (pinfunction "SPEED_19") (pintype "input"))
      (node (ref "RL21") (pin "2") (pinfunction "2_2") (pintype "passive"))
    )
    (net (code "73") (name "Net-(ICDRIVER2-TDEAD)") (class "Default")
      (node (ref "ICDRIVER2") (pin "20") (pinfunction "TDEAD_20") (pintype "input"))
      (node (ref "RDEAD1") (pin "2") (pinfunction "2_2") (pintype "passive"))
    )
    (net (code "74") (name "Net-(ICDRIVER2-VREG)") (class "Default")
      (node (ref "CREG1") (pin "1") (pinfunction "1_1") (pintype "passive"))
      (node (ref "ICDRIVER2") (pin "14") (pinfunction "VREG_14") (pintype "power_in"))
    )
    (net (code "75") (name "Net-(LED1-PadC)") (class "Default")
      (node (ref "LED1") (pin "C") (pinfunction "C_C") (pintype "passive"))
      (node (ref "RL22") (pin "1") (pinfunction "1_1") (pintype "passive"))
    )
    (net (code "76") (name "Net-(LED2-PadC)") (class "Default")
      (node (ref "LED2") (pin "C") (pinfunction "C_C") (pintype "passive"))
      (node (ref "RF11") (pin "1") (pinfunction "1_1") (pintype "passive"))
    )
    (net (code "77") (name "Net-(LED3-PadC)") (class "Default")
      (node (ref "LED3") (pin "C") (pinfunction "C_C") (pintype "passive"))
      (node (ref "RL11") (pin "1") (pinfunction "1_1") (pintype "passive"))
    )
    (net (code "78") (name "Net-(LED4-PadC)") (class "Default")
      (node (ref "LED4") (pin "C") (pinfunction "C_C") (pintype "passive"))
      (node (ref "RF12") (pin "1") (pinfunction "1_1") (pintype "passive"))
    )
    (net (code "79") (name "VOUT1") (class "Default")
      (node (ref "IC1") (pin "1") (pinfunction "OUT_1") (pintype "output"))
      (node (ref "RF1") (pin "2") (pinfunction "2_2") (pintype "passive"))
      (node (ref "U$1") (pin "7") (pinfunction "S_7") (pintype "passive"))
    )
    (net (code "80") (name "VOUT2") (class "Default")
      (node (ref "IC1") (pin "7") (pinfunction "OUT_7") (pintype "output"))
      (node (ref "RF2") (pin "1") (pinfunction "1_1") (pintype "passive"))
      (node (ref "U$2") (pin "7") (pinfunction "S_7") (pintype "passive"))
    )
    (net (code "81") (name "VT") (class "Default")
      (node (ref "J1") (pin "1") (pinfunction "1_1") (pintype "passive"))
      (node (ref "J2") (pin "1") (pinfunction "1_1") (pintype "passive"))
      (node (ref "RF3") (pin "2") (pinfunction "2_2") (pintype "passive"))
      (node (ref "RF4") (pin "1") (pinfunction "1_1") (pintype "passive"))
    )
  )
)
